# CONN.net
KiCad netlist of a schematic drawn in Altium Designer
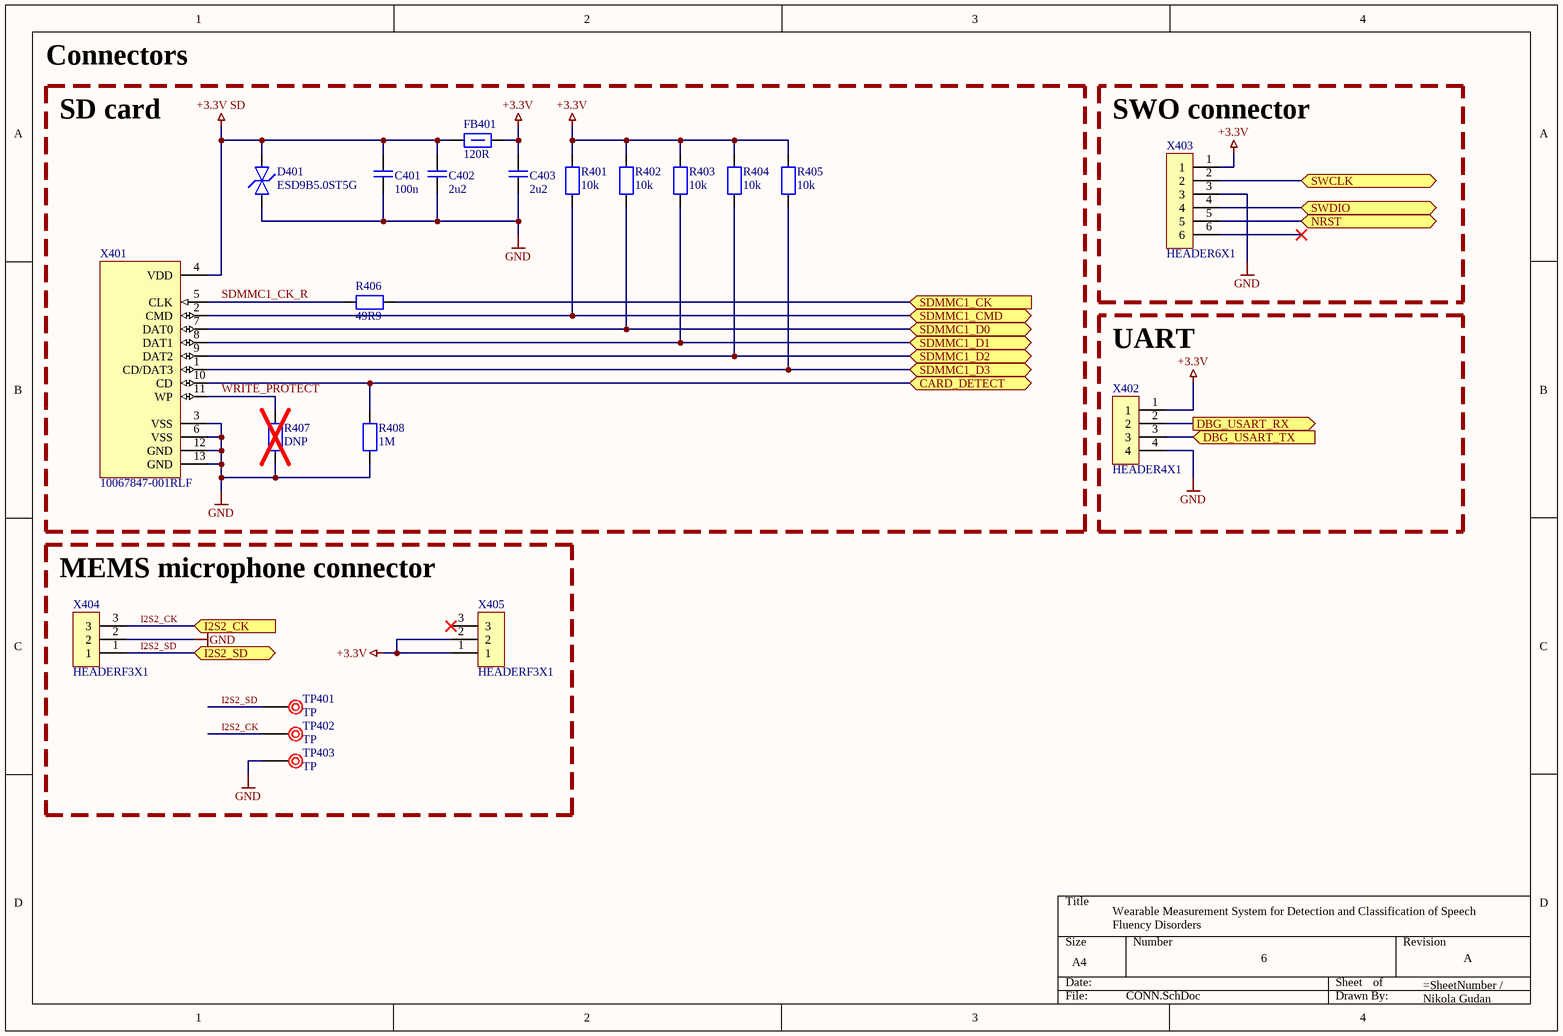
[diagram p0: CONN.SchDoc]

(export (version "E")
  (design (tool "Eeschema 10.0.6"))
  (components
    (comp (ref "C401")
      (value "100n")
      (footprint "CAPC0603")
      (description "Ceramic capacitor, VAL?,  VOL?, DIEL?")
      (fields (field (name "MFR") "?") (field (name "CHECKED") "Yes"))
      (libsource (lib "NG_Passive") (part "CAPC0603"))
    )
    (comp (ref "C402")
      (value "2u2")
      (footprint "CAPC0603")
      (description "Ceramic capacitor, VAL?,  VOL?, DIEL?")
      (fields (field (name "MFR") "?") (field (name "CHECKED") "Yes"))
      (libsource (lib "NG_Passive") (part "CAPC0603"))
    )
    (comp (ref "C403")
      (value "2u2")
      (footprint "CAPC0603")
      (description "Ceramic capacitor, VAL?,  VOL?, DIEL?")
      (fields (field (name "MFR") "?") (field (name "CHECKED") "Yes"))
      (libsource (lib "NG_Passive") (part "CAPC0603"))
    )
    (comp (ref "D401")
      (value "ESD9B5.0ST5G")
      (footprint "DIOC8060X37")
      (description "TVS ZENER DIODE 5VWM")
      (fields
        (field (name "MFR") "onsemi")
        (field (name "LCSC PART NUMBER") "C3021104")
        (field (name "CHECKED") "Yes")
      )
      (libsource (lib "NG_Active") (part "TVS DIODE ESD9B5.0ST5G"))
    )
    (comp (ref "FB401")
      (value "120R")
      (footprint "FBC0603")
      (description "Ferrite bead, 120R@100MHz")
      (fields
        (field (name "MFR") "TDK Corporation")
        (field (name "LCSC PART NUMBER") "C3716437")
        (field (name "CHECKED") "Yes")
      )
      (libsource (lib "NG_Passive") (part "FB0603-120R"))
    )
    (comp (ref "R401")
      (value "10k")
      (footprint "RESC0603")
      (description "Thick film resistor, VAL?, POW?")
      (fields (field (name "MFR") "?") (field (name "CHECKED") "Yes"))
      (libsource (lib "NG_Passive") (part "RES0603"))
    )
    (comp (ref "R402")
      (value "10k")
      (footprint "RESC0603")
      (description "Thick film resistor, VAL?, POW?")
      (fields (field (name "MFR") "?") (field (name "CHECKED") "Yes"))
      (libsource (lib "NG_Passive") (part "RES0603"))
    )
    (comp (ref "R403")
      (value "10k")
      (footprint "RESC0603")
      (description "Thick film resistor, VAL?, POW?")
      (fields (field (name "MFR") "?") (field (name "CHECKED") "Yes"))
      (libsource (lib "NG_Passive") (part "RES0603"))
    )
    (comp (ref "R404")
      (value "10k")
      (footprint "RESC0603")
      (description "Thick film resistor, VAL?, POW?")
      (fields (field (name "MFR") "?") (field (name "CHECKED") "Yes"))
      (libsource (lib "NG_Passive") (part "RES0603"))
    )
    (comp (ref "R405")
      (value "10k")
      (footprint "RESC0603")
      (description "Thick film resistor, VAL?, POW?")
      (fields (field (name "MFR") "?") (field (name "CHECKED") "Yes"))
      (libsource (lib "NG_Passive") (part "RES0603"))
    )
    (comp (ref "R406")
      (value "49R9")
      (footprint "RESC0603")
      (description "Thick film resistor, VAL?, POW?")
      (fields (field (name "MFR") "?") (field (name "CHECKED") "Yes"))
      (libsource (lib "NG_Passive") (part "RES0603"))
    )
    (comp (ref "R407")
      (value "DNP")
      (footprint "RESC0603")
      (description "Thick film resistor, VAL?, POW?")
      (fields (field (name "MFR") "?") (field (name "CHECKED") "Yes"))
      (libsource (lib "NG_Passive") (part "RES0603"))
    )
    (comp (ref "R408")
      (value "1M")
      (footprint "RESC0603")
      (description "Thick film resistor, VAL?, POW?")
      (fields (field (name "MFR") "?") (field (name "CHECKED") "Yes"))
      (libsource (lib "NG_Passive") (part "RES0603"))
    )
    (comp (ref "TP401")
      (value "TP")
      (footprint "TESTPOINT")
      (description "Testpoint")
      (fields
        (field (name "MFR") "Keystone")
        (field (name "LCSC PART NUMBER") "C238122")
        (field (name "CHECKED") "Yes")
      )
      (libsource (lib "NG_Mechanical") (part "TESTPOINT"))
    )
    (comp (ref "TP402")
      (value "TP")
      (footprint "TESTPOINT")
      (description "Testpoint")
      (fields
        (field (name "MFR") "Keystone")
        (field (name "LCSC PART NUMBER") "C238122")
        (field (name "CHECKED") "Yes")
      )
      (libsource (lib "NG_Mechanical") (part "TESTPOINT"))
    )
    (comp (ref "TP403")
      (value "TP")
      (footprint "TESTPOINT")
      (description "Testpoint")
      (fields
        (field (name "MFR") "Keystone")
        (field (name "LCSC PART NUMBER") "C238122")
        (field (name "CHECKED") "Yes")
      )
      (libsource (lib "NG_Mechanical") (part "TESTPOINT"))
    )
    (comp (ref "X401")
      (value "10067847-001RLF")
      (footprint "SD_10067847-001RLF")
      (description "SD card connector, push-push, SMD")
      (fields
        (field (name "MFR") "Amphenol ICC (FCI)")
        (field (name "LCSC PART NUMBER") "C569097")
        (field (name "CHECKED") "Yes")
      )
      (libsource (lib "NG_Mechanical") (part "CONN SD CARD 10067847-001RLF"))
    )
    (comp (ref "X402")
      (value "HEADER4X1")
      (footprint "HDRV4W64P254_4X1_1016X254X1150")
      (description "Pin Header 4x1, P2.54")
      (fields (field (name "MFR") "Würth Elektronik") (field (name "CHECKED") "Yes"))
      (libsource (lib "NG_Mechanical") (part "HEADER4X1"))
    )
    (comp (ref "X403")
      (value "HEADER6X1")
      (footprint "HDR6W64P254_6X1_1524X254X1150")
      (description "Pin header, 6x1, 100mil pitch")
      (fields
        (field (name "MFR") "Adam Tech")
        (field (name "LCSC PART NUMBER") "C2935912")
        (field (name "CHECKED") "Yes")
      )
      (libsource (lib "NG_Mechanical") (part "HEADER6X1"))
    )
    (comp (ref "X404")
      (value "HEADERF3X1")
      (footprint "HDRVF3W64P254_1X3_813X254X850P")
      (description "Pin Header Female 3x1, P2.54")
      (fields (field (name "MFR") "Sullins Connector Solutions") (field (name "CHECKED") "Yes"))
      (libsource (lib "") (part "HEADERF3X1_1"))
    )
    (comp (ref "X405")
      (value "HEADERF3X1")
      (footprint "HDRVF3W64P254_1X3_813X254X850P")
      (description "Pin Header Female 3x1, P2.54")
      (fields (field (name "MFR") "Sullins Connector Solutions") (field (name "CHECKED") "Yes"))
      (libsource (lib "NG_Mechanical") (part "HEADERF3X1"))
    )
  )
  (nets
    (net (code "1") (name "+3.3V") (class "Default")
      (node (ref "C403") (pin "2") (pinfunction "2_2") (pintype "passive"))
      (node (ref "FB401") (pin "2") (pinfunction "2_2") (pintype "passive"))
      (node (ref "R401") (pin "2") (pinfunction "2_2") (pintype "passive"))
      (node (ref "R402") (pin "2") (pinfunction "2_2") (pintype "passive"))
      (node (ref "R403") (pin "2") (pinfunction "2_2") (pintype "passive"))
      (node (ref "R404") (pin "2") (pinfunction "2_2") (pintype "passive"))
      (node (ref "R405") (pin "2") (pinfunction "2_2") (pintype "passive"))
      (node (ref "X402") (pin "1") (pinfunction "1_1") (pintype "passive"))
      (node (ref "X403") (pin "1") (pinfunction "1_1") (pintype "passive"))
      (node (ref "X405") (pin "1") (pinfunction "1_1") (pintype "passive"))
      (node (ref "X405") (pin "2") (pinfunction "2_2") (pintype "passive"))
    )
    (net (code "2") (name "+3.3V SD") (class "Default")
      (node (ref "C401") (pin "2") (pinfunction "2_2") (pintype "passive"))
      (node (ref "C402") (pin "2") (pinfunction "2_2") (pintype "passive"))
      (node (ref "D401") (pin "2") (pinfunction "2_2") (pintype "passive"))
      (node (ref "FB401") (pin "1") (pinfunction "1_1") (pintype "passive"))
      (node (ref "X401") (pin "4") (pinfunction "VDD_4") (pintype "power_in"))
    )
    (net (code "3") (name "/CARD_DETECT") (class "Default")
      (node (ref "R408") (pin "2") (pinfunction "2_2") (pintype "passive"))
      (node (ref "X401") (pin "10") (pinfunction "CD_10") (pintype "bidirectional"))
    )
    (net (code "4") (name "/DBG_USART_RX") (class "Default")
      (node (ref "X402") (pin "2") (pinfunction "2_2") (pintype "passive"))
    )
    (net (code "5") (name "/DBG_USART_TX") (class "Default")
      (node (ref "X402") (pin "3") (pinfunction "3_3") (pintype "passive"))
    )
    (net (code "6") (name "/I2S2_CK") (class "Default")
      (node (ref "TP402") (pin "1") (pinfunction "1_1") (pintype "passive"))
      (node (ref "X404") (pin "3") (pinfunction "3_3") (pintype "passive"))
    )
    (net (code "7") (name "/I2S2_SD") (class "Default")
      (node (ref "TP401") (pin "1") (pinfunction "1_1") (pintype "passive"))
      (node (ref "X404") (pin "1") (pinfunction "1_1") (pintype "passive"))
    )
    (net (code "8") (name "/NRST") (class "Default")
      (node (ref "X403") (pin "5") (pinfunction "5_5") (pintype "passive"))
    )
    (net (code "9") (name "/SDMMC1_CK") (class "Default")
      (node (ref "R406") (pin "1") (pinfunction "1_1") (pintype "passive"))
    )
    (net (code "10") (name "/SDMMC1_CK_R") (class "Default")
      (node (ref "R406") (pin "2") (pinfunction "2_2") (pintype "passive"))
      (node (ref "X401") (pin "5") (pinfunction "CLK_5") (pintype "input"))
    )
    (net (code "11") (name "/SDMMC1_CMD") (class "Default")
      (node (ref "R401") (pin "1") (pinfunction "1_1") (pintype "passive"))
      (node (ref "X401") (pin "2") (pinfunction "CMD_2") (pintype "bidirectional"))
    )
    (net (code "12") (name "/SDMMC1_D0") (class "Default")
      (node (ref "R402") (pin "1") (pinfunction "1_1") (pintype "passive"))
      (node (ref "X401") (pin "7") (pinfunction "DAT0_7") (pintype "bidirectional"))
    )
    (net (code "13") (name "/SDMMC1_D1") (class "Default")
      (node (ref "R403") (pin "1") (pinfunction "1_1") (pintype "passive"))
      (node (ref "X401") (pin "8") (pinfunction "DAT1_8") (pintype "bidirectional"))
    )
    (net (code "14") (name "/SDMMC1_D2") (class "Default")
      (node (ref "R404") (pin "1") (pinfunction "1_1") (pintype "passive"))
      (node (ref "X401") (pin "9") (pinfunction "DAT2_9") (pintype "bidirectional"))
    )
    (net (code "15") (name "/SDMMC1_D3") (class "Default")
      (node (ref "R405") (pin "1") (pinfunction "1_1") (pintype "passive"))
      (node (ref "X401") (pin "1") (pinfunction "CD/DAT3_1") (pintype "bidirectional"))
    )
    (net (code "16") (name "/SWCLK") (class "Default")
      (node (ref "X403") (pin "2") (pinfunction "2_2") (pintype "passive"))
    )
    (net (code "17") (name "/SWDIO") (class "Default")
      (node (ref "X403") (pin "4") (pinfunction "4_4") (pintype "passive"))
    )
    (net (code "18") (name "/WRITE_PROTECT") (class "Default")
      (node (ref "R407") (pin "2") (pinfunction "2_2") (pintype "passive"))
      (node (ref "X401") (pin "11") (pinfunction "WP_11") (pintype "bidirectional"))
    )
    (net (code "19") (name "GND") (class "Default")
      (node (ref "C401") (pin "1") (pinfunction "1_1") (pintype "passive"))
      (node (ref "C402") (pin "1") (pinfunction "1_1") (pintype "passive"))
      (node (ref "C403") (pin "1") (pinfunction "1_1") (pintype "passive"))
      (node (ref "D401") (pin "1") (pinfunction "1_1") (pintype "passive"))
      (node (ref "R407") (pin "1") (pinfunction "1_1") (pintype "passive"))
      (node (ref "R408") (pin "1") (pinfunction "1_1") (pintype "passive"))
      (node (ref "TP403") (pin "1") (pinfunction "1_1") (pintype "passive"))
      (node (ref "X401") (pin "12") (pinfunction "GND_12") (pintype "power_in"))
      (node (ref "X401") (pin "13") (pinfunction "GND_13") (pintype "power_in"))
      (node (ref "X401") (pin "3") (pinfunction "VSS_3") (pintype "power_in"))
      (node (ref "X401") (pin "6") (pinfunction "VSS_6") (pintype "power_in"))
      (node (ref "X402") (pin "4") (pinfunction "4_4") (pintype "passive"))
      (node (ref "X403") (pin "3") (pinfunction "3_3") (pintype "passive"))
      (node (ref "X404") (pin "2") (pinfunction "2_2") (pintype "passive"))
    )
    (net (code "20") (name "unconnected-(X403-Pad6)") (class "Default")
      (node (ref "X403") (pin "6") (pinfunction "6_6") (pintype "passive+no_connect"))
    )
    (net (code "21") (name "unconnected-(X405-Pad3)") (class "Default")
      (node (ref "X405") (pin "3") (pinfunction "3_3") (pintype "passive+no_connect"))
    )
  )
)
